# Sheet1_MCU.net
KiCad netlist of a schematic drawn in Altium Designer
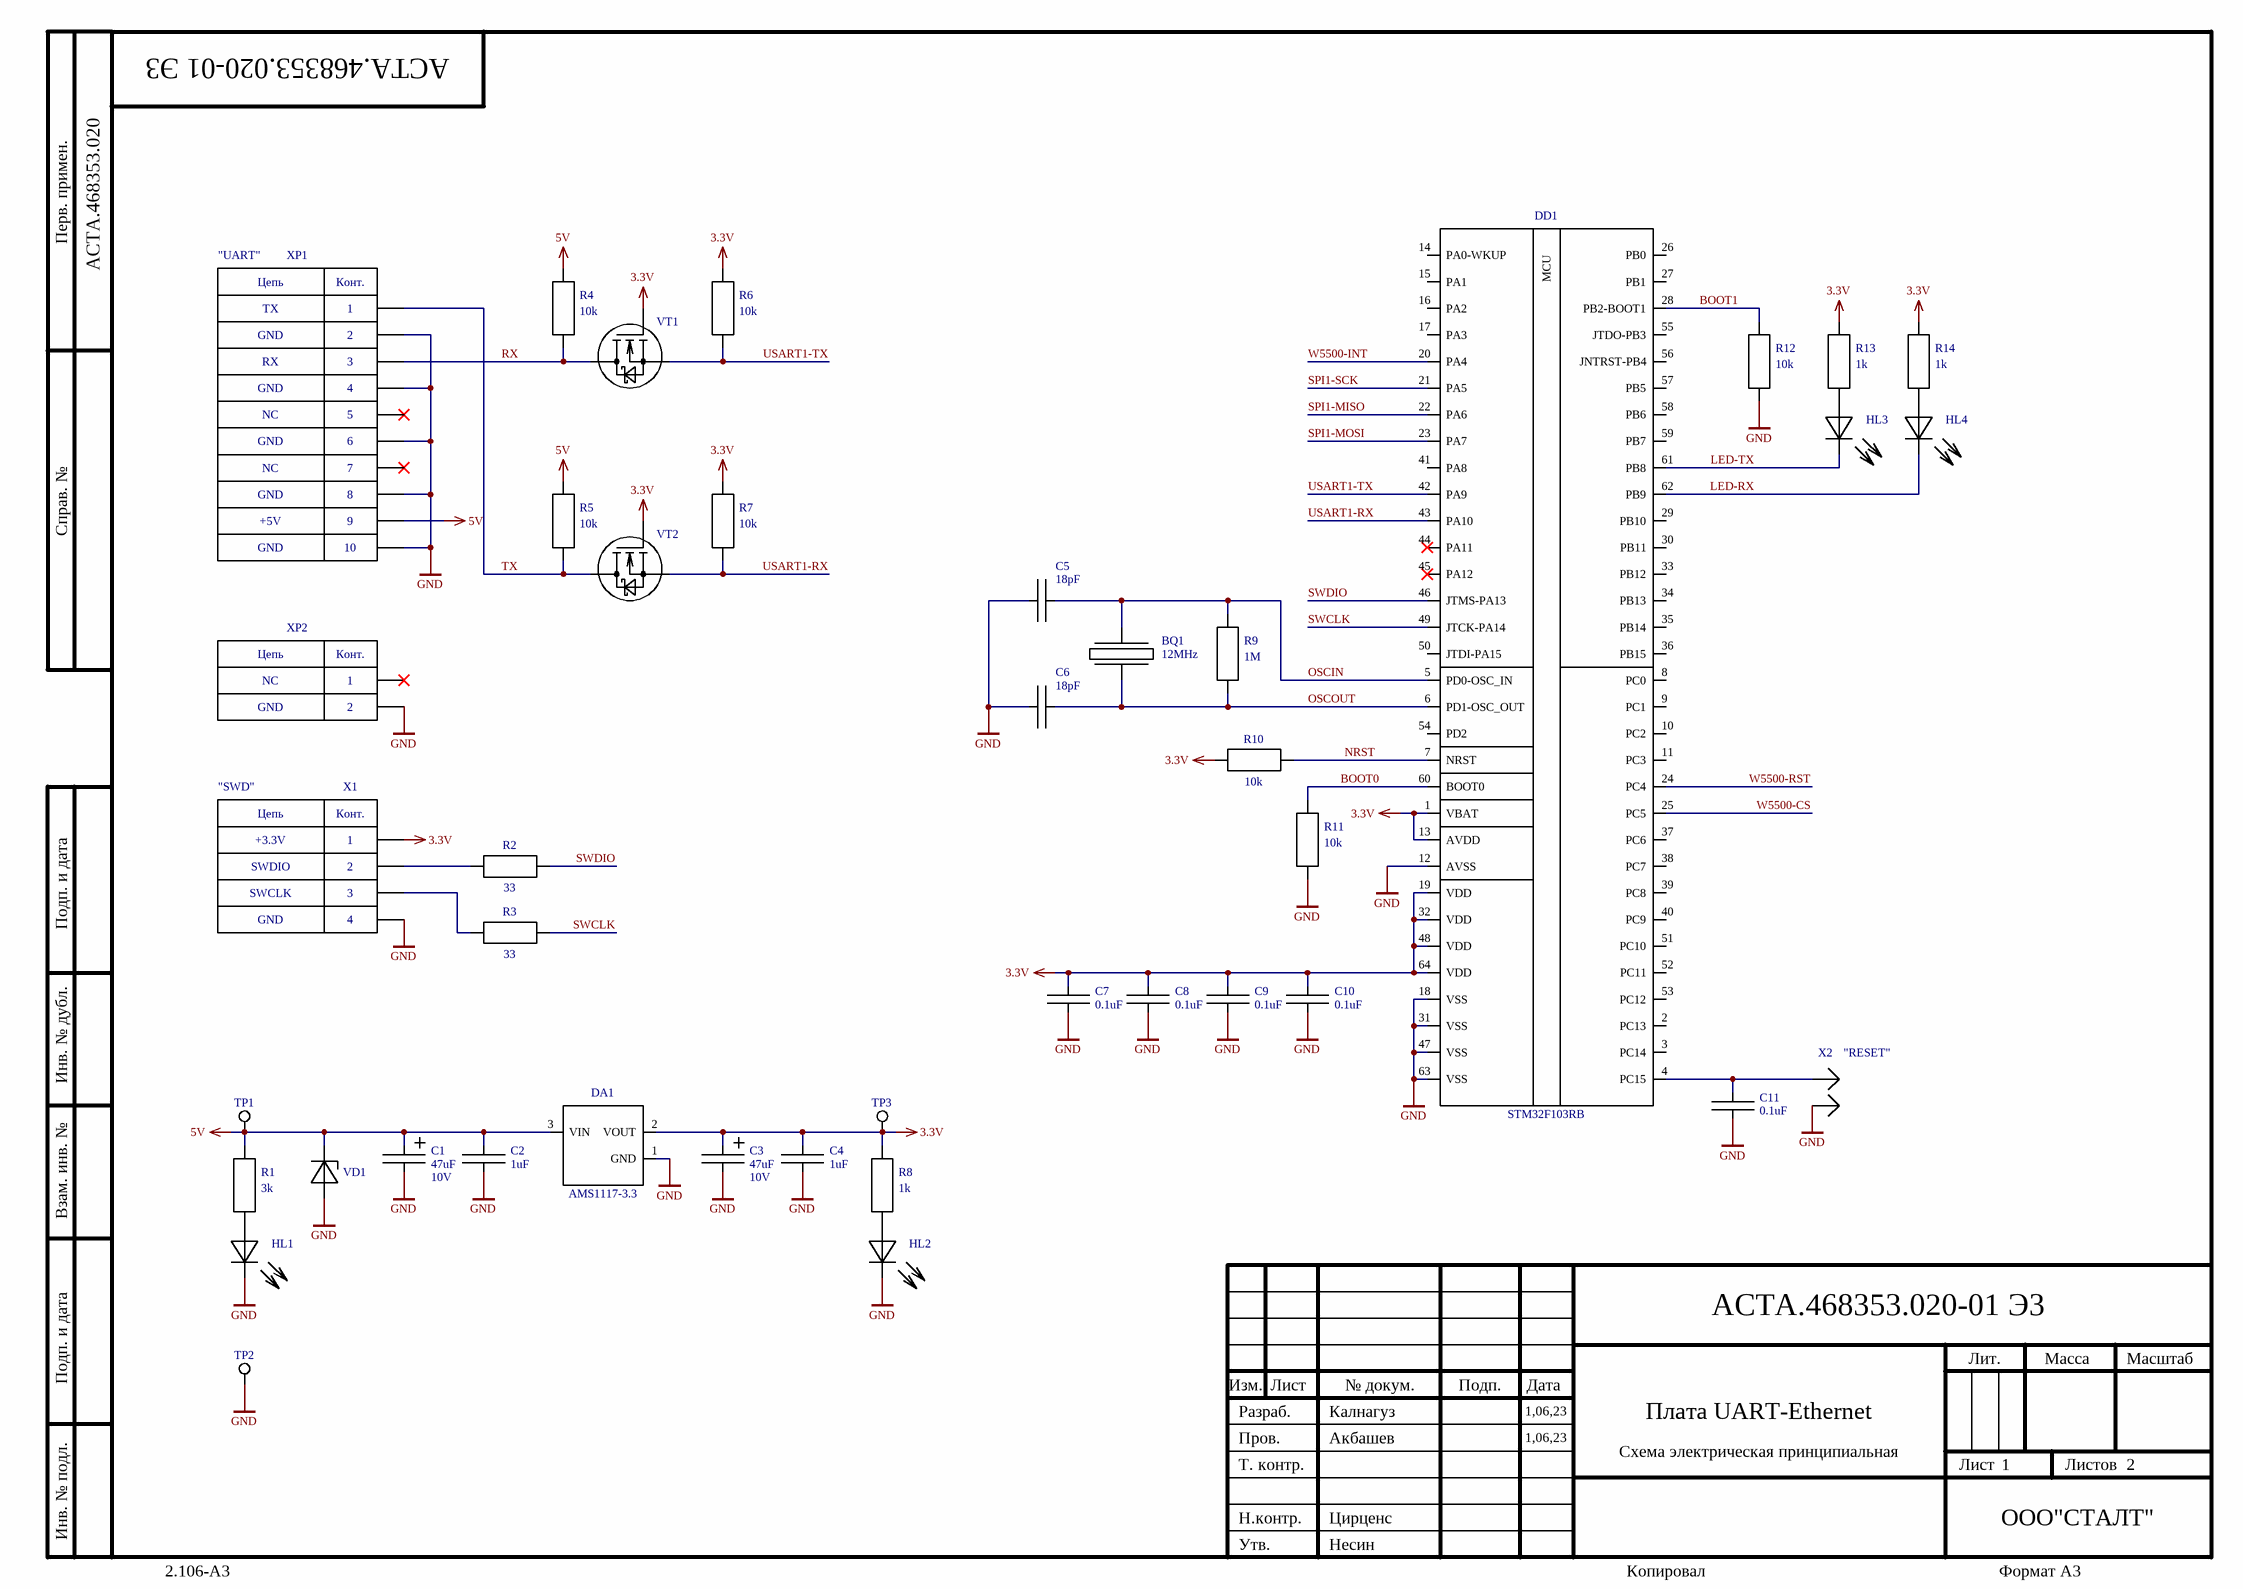
[diagram p0: Sheet1_MCU.SchDoc]

(export (version "E")
  (design (tool "Eeschema 10.0.6"))
  (components
    (comp (ref "BQ1")
      (value "12MHz")
      (footprint "HT-49S")
      (fields (field (name "Comment") "HT-49S_Rated"))
      (libsource (lib "Resonators") (part "HT-49S_Rated"))
    )
    (comp (ref "C1")
      (value "47uF")
      (footprint "CaseB_TantalumCap")
      (fields (field (name "VOLTAGE") "10V") (field (name "Comment") "CaseB_TantalumCap"))
      (libsource (lib "Tantalum_Capacitors") (part "CaseB_TantalumCap"))
    )
    (comp (ref "C2")
      (value "1uF")
      (footprint "CAP0805")
      (fields (field (name "Comment") "CAP0805_Rated"))
      (libsource (lib "Ceramic_Capacitors") (part "CAP0805_Rated"))
    )
    (comp (ref "C3")
      (value "47uF")
      (footprint "CaseB_TantalumCap")
      (fields (field (name "VOLTAGE") "10V") (field (name "Comment") "CaseB_TantalumCap"))
      (libsource (lib "Tantalum_Capacitors") (part "CaseB_TantalumCap"))
    )
    (comp (ref "C4")
      (value "1uF")
      (footprint "CAP0805")
      (fields (field (name "Comment") "CAP0805_Rated"))
      (libsource (lib "Ceramic_Capacitors") (part "CAP0805_Rated"))
    )
    (comp (ref "C5")
      (value "18pF")
      (footprint "CAP0805")
      (fields (field (name "Comment") "CAP0805_Rated"))
      (libsource (lib "Ceramic_Capacitors") (part "CAP0805_Rated"))
    )
    (comp (ref "C6")
      (value "18pF")
      (footprint "CAP0805")
      (fields (field (name "Comment") "CAP0805_Rated"))
      (libsource (lib "Ceramic_Capacitors") (part "CAP0805_Rated"))
    )
    (comp (ref "C7")
      (value "0.1uF")
      (footprint "CAP0805")
      (fields (field (name "Comment") "CAP0805_Rated"))
      (libsource (lib "Ceramic_Capacitors") (part "CAP0805_Rated"))
    )
    (comp (ref "C8")
      (value "0.1uF")
      (footprint "CAP0805")
      (fields (field (name "Comment") "CAP0805_Rated"))
      (libsource (lib "Ceramic_Capacitors") (part "CAP0805_Rated"))
    )
    (comp (ref "C9")
      (value "0.1uF")
      (footprint "CAP0805")
      (fields (field (name "Comment") "CAP0805_Rated"))
      (libsource (lib "Ceramic_Capacitors") (part "CAP0805_Rated"))
    )
    (comp (ref "C10")
      (value "0.1uF")
      (footprint "CAP0805")
      (fields (field (name "Comment") "CAP0805_Rated"))
      (libsource (lib "Ceramic_Capacitors") (part "CAP0805_Rated"))
    )
    (comp (ref "C11")
      (value "0.1uF")
      (footprint "CAP0805")
      (fields (field (name "Comment") "CAP0805_Rated"))
      (libsource (lib "Ceramic_Capacitors") (part "CAP0805_Rated"))
    )
    (comp (ref "DA1")
      (value "AMS1117-3.3")
      (footprint "SOT-223")
      (description "Fixed Voltage 3.3V 1A Low Dropout Voltage Regulator")
      (libsource (lib "Power_Management_ICs") (part "AMS1117-3.3"))
    )
    (comp (ref "DD1")
      (value "STM32F103RB")
      (footprint "LQFP-64")
      (description "ARM Cortex-M3 MCU")
      (libsource (lib "MCU") (part "STM32F103RB"))
    )
    (comp (ref "HL1")
      (value "KPTD-3216MGC")
      (footprint "KPTD-3216 Green")
      (description "3.2x1.6mm SMD LED Mega Green")
      (libsource (lib "LEDs_SMD") (part "KPTD-3216MGC"))
    )
    (comp (ref "HL2")
      (value "KPTD-3216MGC")
      (footprint "KPTD-3216 Green")
      (description "3.2x1.6mm SMD LED Mega Green")
      (libsource (lib "LEDs_SMD") (part "KPTD-3216MGC"))
    )
    (comp (ref "HL3")
      (value "KPTD-3216MGC")
      (footprint "KPTD-3216 Green")
      (description "3.2x1.6mm SMD LED Mega Green")
      (libsource (lib "LEDs_SMD") (part "KPTD-3216MGC"))
    )
    (comp (ref "HL4")
      (value "KPTD-3216SYC")
      (footprint "KPTD-3216 Yellow")
      (description "3.2x1.6mm SMD LED Super Bright Yellow")
      (libsource (lib "LEDs_SMD") (part "KPTD-3216SYC"))
    )
    (comp (ref "R1")
      (value "3k")
      (footprint "RES0805")
      (fields (field (name "TOLERANCE") "5%") (field (name "Comment") "RES0805_Rated"))
      (libsource (lib "Resistors") (part "RES0805_Rated"))
    )
    (comp (ref "R2")
      (value "33")
      (footprint "RES0805")
      (fields (field (name "TOLERANCE") "5%") (field (name "Comment") "RES0805_Rated"))
      (libsource (lib "") (part "RES0805_Rated_1"))
    )
    (comp (ref "R3")
      (value "33")
      (footprint "RES0805")
      (fields (field (name "TOLERANCE") "5%") (field (name "Comment") "RES0805_Rated"))
      (libsource (lib "") (part "RES0805_Rated_1"))
    )
    (comp (ref "R4")
      (value "10k")
      (footprint "RES0805")
      (fields (field (name "TOLERANCE") "5%") (field (name "Comment") "RES0805_Rated"))
      (libsource (lib "Resistors") (part "RES0805_Rated"))
    )
    (comp (ref "R5")
      (value "10k")
      (footprint "RES0805")
      (fields (field (name "TOLERANCE") "5%") (field (name "Comment") "RES0805_Rated"))
      (libsource (lib "Resistors") (part "RES0805_Rated"))
    )
    (comp (ref "R6")
      (value "10k")
      (footprint "RES0805")
      (fields (field (name "TOLERANCE") "5%") (field (name "Comment") "RES0805_Rated"))
      (libsource (lib "Resistors") (part "RES0805_Rated"))
    )
    (comp (ref "R7")
      (value "10k")
      (footprint "RES0805")
      (fields (field (name "TOLERANCE") "5%") (field (name "Comment") "RES0805_Rated"))
      (libsource (lib "Resistors") (part "RES0805_Rated"))
    )
    (comp (ref "R8")
      (value "1k")
      (footprint "RES0805")
      (fields (field (name "TOLERANCE") "5%") (field (name "Comment") "RES0805_Rated"))
      (libsource (lib "Resistors") (part "RES0805_Rated"))
    )
    (comp (ref "R9")
      (value "1M")
      (footprint "RES0805")
      (fields (field (name "TOLERANCE") "5%") (field (name "Comment") "RES0805_Rated"))
      (libsource (lib "Resistors") (part "RES0805_Rated"))
    )
    (comp (ref "R10")
      (value "10k")
      (footprint "RES0805")
      (fields (field (name "TOLERANCE") "5%") (field (name "Comment") "RES0805_Rated"))
      (libsource (lib "") (part "RES0805_Rated_1"))
    )
    (comp (ref "R11")
      (value "10k")
      (footprint "RES0805")
      (fields (field (name "TOLERANCE") "5%") (field (name "Comment") "RES0805_Rated"))
      (libsource (lib "Resistors") (part "RES0805_Rated"))
    )
    (comp (ref "R12")
      (value "10k")
      (footprint "RES0805")
      (fields (field (name "TOLERANCE") "5%") (field (name "Comment") "RES0805_Rated"))
      (libsource (lib "Resistors") (part "RES0805_Rated"))
    )
    (comp (ref "R13")
      (value "1k")
      (footprint "RES0805")
      (fields (field (name "TOLERANCE") "5%") (field (name "Comment") "RES0805_Rated"))
      (libsource (lib "Resistors") (part "RES0805_Rated"))
    )
    (comp (ref "R14")
      (value "1k")
      (footprint "RES0805")
      (fields (field (name "TOLERANCE") "5%") (field (name "Comment") "RES0805_Rated"))
      (libsource (lib "Resistors") (part "RES0805_Rated"))
    )
    (comp (ref "TP1")
      (value "TestPad")
      (footprint "PAD-TH-OCT1x1-0.5")
      (description "TestPoint on PCB")
      (libsource (lib "Connectors") (part "TestPad"))
    )
    (comp (ref "TP2")
      (value "TestPad")
      (footprint "PAD-TH-OCT1x1-0.5")
      (description "TestPoint on PCB")
      (libsource (lib "Connectors") (part "TestPad"))
    )
    (comp (ref "TP3")
      (value "TestPad")
      (footprint "PAD-TH-OCT1x1-0.5")
      (description "TestPoint on PCB")
      (libsource (lib "Connectors") (part "TestPad"))
    )
    (comp (ref "VD1")
      (value "SMAJ5.0A")
      (footprint "SMA (DO-214AC)")
      (description "5Vr 400W 43.5A UniDirectional TVS")
      (libsource (lib "TVS_Diodes") (part "SMAJ5.0A"))
    )
    (comp (ref "VT1")
      (value "BSS138")
      (footprint "SOT-23")
      (description "Small Signal N-Channel MOSFET 50V 220mA")
      (libsource (lib "MOSFETs") (part "BSS138"))
    )
    (comp (ref "VT2")
      (value "BSS138")
      (footprint "SOT-23")
      (description "Small Signal N-Channel MOSFET 50V 220mA")
      (libsource (lib "MOSFETs") (part "BSS138"))
    )
    (comp (ref "X1")
      (value "PBS-4")
      (footprint "PBS-4")
      (description "Female Header Pitch 2.54mm")
      (fields
        (field (name "CIRCUIT4") "GND")
        (field (name "CIRCUIT3") "SWCLK")
        (field (name "CIRCUIT1") "+3.3V")
        (field (name "CIRCUIT2") "SWDIO")
        (field (name "LABEL") "\"SWD\"")
      )
      (libsource (lib "Connectors") (part "PBS-4"))
    )
    (comp (ref "X2")
      (value "PLS-2")
      (footprint "PLS-2")
      (description "Pin Header Pitch 2.54mm")
      (fields (field (name "LABEL") "\"RESET\""))
      (libsource (lib "") (part "PLS-2_1"))
    )
    (comp (ref "XP1")
      (value "PLS-10")
      (footprint "PLS-10")
      (description "Pin Header Pitch 2.54mm")
      (fields
        (field (name "CIRCUIT4") "GND")
        (field (name "CIRCUIT5") "NC")
        (field (name "CIRCUIT6") "GND")
        (field (name "CIRCUIT7") "NC")
        (field (name "CIRCUIT8") "GND")
        (field (name "CIRCUIT9") "+5V")
        (field (name "CIRCUIT10") "GND")
        (field (name "CIRCUIT3") "RX")
        (field (name "CIRCUIT1") "TX")
        (field (name "CIRCUIT2") "GND")
        (field (name "LABEL") "\"UART\"")
      )
      (libsource (lib "Connectors") (part "PLS-10"))
    )
    (comp (ref "XP2")
      (value "PLS-2")
      (footprint "PLS-2")
      (description "Pin Header Pitch 2.54mm")
      (fields (field (name "CIRCUIT1") "NC") (field (name "CIRCUIT2") "GND"))
      (libsource (lib "Connectors") (part "PLS-2"))
    )
  )
  (nets
    (net (code "1") (name "/BOOT0") (class "Default")
      (node (ref "DD1") (pin "60") (pinfunction "BOOT0_60") (pintype "power_in"))
      (node (ref "R11") (pin "2") (pinfunction "2_2") (pintype "passive"))
    )
    (net (code "2") (name "/BOOT1") (class "Default")
      (node (ref "DD1") (pin "28") (pinfunction "PB2-BOOT1_28") (pintype "bidirectional"))
      (node (ref "R12") (pin "2") (pinfunction "2_2") (pintype "passive"))
    )
    (net (code "3") (name "/LED-RX") (class "Default")
      (node (ref "DD1") (pin "62") (pinfunction "PB9_62") (pintype "bidirectional"))
      (node (ref "HL4") (pin "K") (pinfunction "K_K") (pintype "passive"))
    )
    (net (code "4") (name "/LED-TX") (class "Default")
      (node (ref "DD1") (pin "61") (pinfunction "PB8_61") (pintype "bidirectional"))
      (node (ref "HL3") (pin "K") (pinfunction "K_K") (pintype "passive"))
    )
    (net (code "5") (name "/NRST") (class "Default")
      (node (ref "DD1") (pin "7") (pinfunction "NRST_7") (pintype "bidirectional"))
      (node (ref "R10") (pin "2") (pinfunction "2_2") (pintype "passive"))
    )
    (net (code "6") (name "/OSCIN") (class "Default")
      (node (ref "BQ1") (pin "1") (pinfunction "1_1") (pintype "passive"))
      (node (ref "C5") (pin "2") (pinfunction "2_2") (pintype "passive"))
      (node (ref "DD1") (pin "5") (pinfunction "PD0-OSC_IN_5") (pintype "bidirectional"))
      (node (ref "R9") (pin "2") (pinfunction "2_2") (pintype "passive"))
    )
    (net (code "7") (name "/OSCOUT") (class "Default")
      (node (ref "BQ1") (pin "2") (pinfunction "2_2") (pintype "passive"))
      (node (ref "C6") (pin "2") (pinfunction "2_2") (pintype "passive"))
      (node (ref "DD1") (pin "6") (pinfunction "PD1-OSC_OUT_6") (pintype "bidirectional"))
      (node (ref "R9") (pin "1") (pinfunction "1_1") (pintype "passive"))
    )
    (net (code "8") (name "/RX") (class "Default")
      (node (ref "R4") (pin "1") (pinfunction "1_1") (pintype "passive"))
      (node (ref "VT1") (pin "2") (pinfunction "D_2") (pintype "passive"))
      (node (ref "XP1") (pin "3") (pinfunction "3_3") (pintype "passive"))
    )
    (net (code "9") (name "/SPI1-MISO") (class "Default")
      (node (ref "DD1") (pin "22") (pinfunction "PA6_22") (pintype "bidirectional"))
    )
    (net (code "10") (name "/SPI1-MOSI") (class "Default")
      (node (ref "DD1") (pin "23") (pinfunction "PA7_23") (pintype "bidirectional"))
    )
    (net (code "11") (name "/SPI1-SCK") (class "Default")
      (node (ref "DD1") (pin "21") (pinfunction "PA5_21") (pintype "bidirectional"))
    )
    (net (code "12") (name "/SWCLK") (class "Default")
      (node (ref "DD1") (pin "49") (pinfunction "JTCK-PA14_49") (pintype "bidirectional"))
      (node (ref "R3") (pin "2") (pinfunction "2_2") (pintype "passive"))
    )
    (net (code "13") (name "/SWDIO") (class "Default")
      (node (ref "DD1") (pin "46") (pinfunction "JTMS-PA13_46") (pintype "bidirectional"))
      (node (ref "R2") (pin "2") (pinfunction "2_2") (pintype "passive"))
    )
    (net (code "14") (name "/TX") (class "Default")
      (node (ref "R5") (pin "1") (pinfunction "1_1") (pintype "passive"))
      (node (ref "VT2") (pin "2") (pinfunction "D_2") (pintype "passive"))
      (node (ref "XP1") (pin "1") (pinfunction "1_1") (pintype "passive"))
    )
    (net (code "15") (name "/USART1-RX") (class "Default")
      (node (ref "DD1") (pin "43") (pinfunction "PA10_43") (pintype "bidirectional"))
      (node (ref "R7") (pin "1") (pinfunction "1_1") (pintype "passive"))
      (node (ref "VT2") (pin "3") (pinfunction "S_3") (pintype "passive"))
    )
    (net (code "16") (name "/USART1-TX") (class "Default")
      (node (ref "DD1") (pin "42") (pinfunction "PA9_42") (pintype "bidirectional"))
      (node (ref "R6") (pin "1") (pinfunction "1_1") (pintype "passive"))
      (node (ref "VT1") (pin "3") (pinfunction "S_3") (pintype "passive"))
    )
    (net (code "17") (name "/W5500-CS") (class "Default")
      (node (ref "DD1") (pin "25") (pinfunction "PC5_25") (pintype "bidirectional"))
    )
    (net (code "18") (name "/W5500-INT") (class "Default")
      (node (ref "DD1") (pin "20") (pinfunction "PA4_20") (pintype "bidirectional"))
    )
    (net (code "19") (name "/W5500-RST") (class "Default")
      (node (ref "DD1") (pin "24") (pinfunction "PC4_24") (pintype "bidirectional"))
    )
    (net (code "20") (name "3.3V") (class "Default")
      (node (ref "C10") (pin "1") (pinfunction "1_1") (pintype "passive"))
      (node (ref "C3") (pin "1") (pinfunction "+_1") (pintype "passive"))
      (node (ref "C4") (pin "1") (pinfunction "1_1") (pintype "passive"))
      (node (ref "C7") (pin "1") (pinfunction "1_1") (pintype "passive"))
      (node (ref "C8") (pin "1") (pinfunction "1_1") (pintype "passive"))
      (node (ref "C9") (pin "1") (pinfunction "1_1") (pintype "passive"))
      (node (ref "DA1") (pin "2") (pinfunction "VOUT_2") (pintype "power_in"))
      (node (ref "DD1") (pin "1") (pinfunction "VBAT_1") (pintype "power_in"))
      (node (ref "DD1") (pin "13") (pinfunction "AVDD_13") (pintype "power_in"))
      (node (ref "DD1") (pin "19") (pinfunction "VDD_19") (pintype "power_in"))
      (node (ref "DD1") (pin "32") (pinfunction "VDD_32") (pintype "power_in"))
      (node (ref "DD1") (pin "48") (pinfunction "VDD_48") (pintype "power_in"))
      (node (ref "DD1") (pin "64") (pinfunction "VDD_64") (pintype "power_in"))
      (node (ref "R10") (pin "1") (pinfunction "1_1") (pintype "passive"))
      (node (ref "R13") (pin "2") (pinfunction "2_2") (pintype "passive"))
      (node (ref "R14") (pin "2") (pinfunction "2_2") (pintype "passive"))
      (node (ref "R6") (pin "2") (pinfunction "2_2") (pintype "passive"))
      (node (ref "R7") (pin "2") (pinfunction "2_2") (pintype "passive"))
      (node (ref "R8") (pin "2") (pinfunction "2_2") (pintype "passive"))
      (node (ref "TP3") (pin "1") (pinfunction "1_1") (pintype "passive"))
      (node (ref "VT1") (pin "1") (pinfunction "G_1") (pintype "passive"))
      (node (ref "VT2") (pin "1") (pinfunction "G_1") (pintype "passive"))
      (node (ref "X1") (pin "1") (pinfunction "1_1") (pintype "passive"))
    )
    (net (code "21") (name "5V") (class "Default")
      (node (ref "C1") (pin "1") (pinfunction "+_1") (pintype "passive"))
      (node (ref "C2") (pin "1") (pinfunction "1_1") (pintype "passive"))
      (node (ref "DA1") (pin "3") (pinfunction "VIN_3") (pintype "power_in"))
      (node (ref "R1") (pin "2") (pinfunction "2_2") (pintype "passive"))
      (node (ref "R4") (pin "2") (pinfunction "2_2") (pintype "passive"))
      (node (ref "R5") (pin "2") (pinfunction "2_2") (pintype "passive"))
      (node (ref "TP1") (pin "1") (pinfunction "1_1") (pintype "passive"))
      (node (ref "VD1") (pin "K") (pinfunction "K_K") (pintype "passive"))
      (node (ref "XP1") (pin "9") (pinfunction "9_9") (pintype "passive"))
    )
    (net (code "22") (name "GND") (class "Default")
      (node (ref "C1") (pin "2") (pinfunction "-_2") (pintype "passive"))
      (node (ref "C10") (pin "2") (pinfunction "2_2") (pintype "passive"))
      (node (ref "C11") (pin "2") (pinfunction "2_2") (pintype "passive"))
      (node (ref "C2") (pin "2") (pinfunction "2_2") (pintype "passive"))
      (node (ref "C3") (pin "2") (pinfunction "-_2") (pintype "passive"))
      (node (ref "C4") (pin "2") (pinfunction "2_2") (pintype "passive"))
      (node (ref "C5") (pin "1") (pinfunction "1_1") (pintype "passive"))
      (node (ref "C6") (pin "1") (pinfunction "1_1") (pintype "passive"))
      (node (ref "C7") (pin "2") (pinfunction "2_2") (pintype "passive"))
      (node (ref "C8") (pin "2") (pinfunction "2_2") (pintype "passive"))
      (node (ref "C9") (pin "2") (pinfunction "2_2") (pintype "passive"))
      (node (ref "DA1") (pin "1") (pinfunction "GND_1") (pintype "power_in"))
      (node (ref "DD1") (pin "12") (pinfunction "AVSS_12") (pintype "power_in"))
      (node (ref "DD1") (pin "18") (pinfunction "VSS_18") (pintype "power_in"))
      (node (ref "DD1") (pin "31") (pinfunction "VSS_31") (pintype "power_in"))
      (node (ref "DD1") (pin "47") (pinfunction "VSS_47") (pintype "power_in"))
      (node (ref "DD1") (pin "63") (pinfunction "VSS_63") (pintype "power_in"))
      (node (ref "HL1") (pin "K") (pinfunction "K_K") (pintype "passive"))
      (node (ref "HL2") (pin "K") (pinfunction "K_K") (pintype "passive"))
      (node (ref "R11") (pin "1") (pinfunction "1_1") (pintype "passive"))
      (node (ref "R12") (pin "1") (pinfunction "1_1") (pintype "passive"))
      (node (ref "TP2") (pin "1") (pinfunction "1_1") (pintype "passive"))
      (node (ref "VD1") (pin "A") (pinfunction "A_A") (pintype "passive"))
      (node (ref "X1") (pin "4") (pinfunction "4_4") (pintype "passive"))
      (node (ref "X2") (pin "2") (pinfunction "2_2") (pintype "passive"))
      (node (ref "XP1") (pin "10") (pinfunction "10_10") (pintype "passive"))
      (node (ref "XP1") (pin "2") (pinfunction "2_2") (pintype "passive"))
      (node (ref "XP1") (pin "4") (pinfunction "4_4") (pintype "passive"))
      (node (ref "XP1") (pin "6") (pinfunction "6_6") (pintype "passive"))
      (node (ref "XP1") (pin "8") (pinfunction "8_8") (pintype "passive"))
      (node (ref "XP2") (pin "2") (pinfunction "2_2") (pintype "passive"))
    )
    (net (code "23") (name "Net-(DD1-PC15)") (class "Default")
      (node (ref "C11") (pin "1") (pinfunction "1_1") (pintype "passive"))
      (node (ref "DD1") (pin "4") (pinfunction "PC15_4") (pintype "bidirectional"))
      (node (ref "X2") (pin "1") (pinfunction "1_1") (pintype "passive"))
    )
    (net (code "24") (name "Net-(HL1-PadA)") (class "Default")
      (node (ref "HL1") (pin "A") (pinfunction "A_A") (pintype "passive"))
      (node (ref "R1") (pin "1") (pinfunction "1_1") (pintype "passive"))
    )
    (net (code "25") (name "Net-(HL2-PadA)") (class "Default")
      (node (ref "HL2") (pin "A") (pinfunction "A_A") (pintype "passive"))
      (node (ref "R8") (pin "1") (pinfunction "1_1") (pintype "passive"))
    )
    (net (code "26") (name "Net-(HL3-PadA)") (class "Default")
      (node (ref "HL3") (pin "A") (pinfunction "A_A") (pintype "passive"))
      (node (ref "R13") (pin "1") (pinfunction "1_1") (pintype "passive"))
    )
    (net (code "27") (name "Net-(HL4-PadA)") (class "Default")
      (node (ref "HL4") (pin "A") (pinfunction "A_A") (pintype "passive"))
      (node (ref "R14") (pin "1") (pinfunction "1_1") (pintype "passive"))
    )
    (net (code "28") (name "Net-(R2-Pad1)") (class "Default")
      (node (ref "R2") (pin "1") (pinfunction "1_1") (pintype "passive"))
      (node (ref "X1") (pin "2") (pinfunction "2_2") (pintype "passive"))
    )
    (net (code "29") (name "Net-(R3-Pad1)") (class "Default")
      (node (ref "R3") (pin "1") (pinfunction "1_1") (pintype "passive"))
      (node (ref "X1") (pin "3") (pinfunction "3_3") (pintype "passive"))
    )
    (net (code "30") (name "unconnected-(DD1-JNTRST-PB4-Pad56)") (class "Default")
      (node (ref "DD1") (pin "56") (pinfunction "JNTRST-PB4_56") (pintype "bidirectional"))
    )
    (net (code "31") (name "unconnected-(DD1-JTDI-PA15-Pad50)") (class "Default")
      (node (ref "DD1") (pin "50") (pinfunction "JTDI-PA15_50") (pintype "bidirectional"))
    )
    (net (code "32") (name "unconnected-(DD1-JTDO-PB3-Pad55)") (class "Default")
      (node (ref "DD1") (pin "55") (pinfunction "JTDO-PB3_55") (pintype "bidirectional"))
    )
    (net (code "33") (name "unconnected-(DD1-PA0-WKUP-Pad14)") (class "Default")
      (node (ref "DD1") (pin "14") (pinfunction "PA0-WKUP_14") (pintype "bidirectional"))
    )
    (net (code "34") (name "unconnected-(DD1-PA1-Pad15)") (class "Default")
      (node (ref "DD1") (pin "15") (pinfunction "PA1_15") (pintype "bidirectional"))
    )
    (net (code "35") (name "unconnected-(DD1-PA2-Pad16)") (class "Default")
      (node (ref "DD1") (pin "16") (pinfunction "PA2_16") (pintype "bidirectional"))
    )
    (net (code "36") (name "unconnected-(DD1-PA3-Pad17)") (class "Default")
      (node (ref "DD1") (pin "17") (pinfunction "PA3_17") (pintype "bidirectional"))
    )
    (net (code "37") (name "unconnected-(DD1-PA8-Pad41)") (class "Default")
      (node (ref "DD1") (pin "41") (pinfunction "PA8_41") (pintype "bidirectional"))
    )
    (net (code "38") (name "unconnected-(DD1-PA11-Pad44)") (class "Default")
      (node (ref "DD1") (pin "44") (pinfunction "PA11_44") (pintype "bidirectional+no_connect"))
    )
    (net (code "39") (name "unconnected-(DD1-PA12-Pad45)") (class "Default")
      (node (ref "DD1") (pin "45") (pinfunction "PA12_45") (pintype "bidirectional+no_connect"))
    )
    (net (code "40") (name "unconnected-(DD1-PB0-Pad26)") (class "Default")
      (node (ref "DD1") (pin "26") (pinfunction "PB0_26") (pintype "bidirectional"))
    )
    (net (code "41") (name "unconnected-(DD1-PB1-Pad27)") (class "Default")
      (node (ref "DD1") (pin "27") (pinfunction "PB1_27") (pintype "bidirectional"))
    )
    (net (code "42") (name "unconnected-(DD1-PB5-Pad57)") (class "Default")
      (node (ref "DD1") (pin "57") (pinfunction "PB5_57") (pintype "bidirectional"))
    )
    (net (code "43") (name "unconnected-(DD1-PB6-Pad58)") (class "Default")
      (node (ref "DD1") (pin "58") (pinfunction "PB6_58") (pintype "bidirectional"))
    )
    (net (code "44") (name "unconnected-(DD1-PB7-Pad59)") (class "Default")
      (node (ref "DD1") (pin "59") (pinfunction "PB7_59") (pintype "bidirectional"))
    )
    (net (code "45") (name "unconnected-(DD1-PB10-Pad29)") (class "Default")
      (node (ref "DD1") (pin "29") (pinfunction "PB10_29") (pintype "bidirectional"))
    )
    (net (code "46") (name "unconnected-(DD1-PB11-Pad30)") (class "Default")
      (node (ref "DD1") (pin "30") (pinfunction "PB11_30") (pintype "bidirectional"))
    )
    (net (code "47") (name "unconnected-(DD1-PB12-Pad33)") (class "Default")
      (node (ref "DD1") (pin "33") (pinfunction "PB12_33") (pintype "bidirectional"))
    )
    (net (code "48") (name "unconnected-(DD1-PB13-Pad34)") (class "Default")
      (node (ref "DD1") (pin "34") (pinfunction "PB13_34") (pintype "bidirectional"))
    )
    (net (code "49") (name "unconnected-(DD1-PB14-Pad35)") (class "Default")
      (node (ref "DD1") (pin "35") (pinfunction "PB14_35") (pintype "bidirectional"))
    )
    (net (code "50") (name "unconnected-(DD1-PB15-Pad36)") (class "Default")
      (node (ref "DD1") (pin "36") (pinfunction "PB15_36") (pintype "bidirectional"))
    )
    (net (code "51") (name "unconnected-(DD1-PC0-Pad8)") (class "Default")
      (node (ref "DD1") (pin "8") (pinfunction "PC0_8") (pintype "bidirectional"))
    )
    (net (code "52") (name "unconnected-(DD1-PC1-Pad9)") (class "Default")
      (node (ref "DD1") (pin "9") (pinfunction "PC1_9") (pintype "bidirectional"))
    )
    (net (code "53") (name "unconnected-(DD1-PC2-Pad10)") (class "Default")
      (node (ref "DD1") (pin "10") (pinfunction "PC2_10") (pintype "bidirectional"))
    )
    (net (code "54") (name "unconnected-(DD1-PC3-Pad11)") (class "Default")
      (node (ref "DD1") (pin "11") (pinfunction "PC3_11") (pintype "bidirectional"))
    )
    (net (code "55") (name "unconnected-(DD1-PC6-Pad37)") (class "Default")
      (node (ref "DD1") (pin "37") (pinfunction "PC6_37") (pintype "bidirectional"))
    )
    (net (code "56") (name "unconnected-(DD1-PC7-Pad38)") (class "Default")
      (node (ref "DD1") (pin "38") (pinfunction "PC7_38") (pintype "bidirectional"))
    )
    (net (code "57") (name "unconnected-(DD1-PC8-Pad39)") (class "Default")
      (node (ref "DD1") (pin "39") (pinfunction "PC8_39") (pintype "bidirectional"))
    )
    (net (code "58") (name "unconnected-(DD1-PC9-Pad40)") (class "Default")
      (node (ref "DD1") (pin "40") (pinfunction "PC9_40") (pintype "bidirectional"))
    )
    (net (code "59") (name "unconnected-(DD1-PC10-Pad51)") (class "Default")
      (node (ref "DD1") (pin "51") (pinfunction "PC10_51") (pintype "bidirectional"))
    )
    (net (code "60") (name "unconnected-(DD1-PC11-Pad52)") (class "Default")
      (node (ref "DD1") (pin "52") (pinfunction "PC11_52") (pintype "bidirectional"))
    )
    (net (code "61") (name "unconnected-(DD1-PC12-Pad53)") (class "Default")
      (node (ref "DD1") (pin "53") (pinfunction "PC12_53") (pintype "bidirectional"))
    )
    (net (code "62") (name "unconnected-(DD1-PC13-Pad2)") (class "Default")
      (node (ref "DD1") (pin "2") (pinfunction "PC13_2") (pintype "bidirectional"))
    )
    (net (code "63") (name "unconnected-(DD1-PC14-Pad3)") (class "Default")
      (node (ref "DD1") (pin "3") (pinfunction "PC14_3") (pintype "bidirectional"))
    )
    (net (code "64") (name "unconnected-(DD1-PD2-Pad54)") (class "Default")
      (node (ref "DD1") (pin "54") (pinfunction "PD2_54") (pintype "bidirectional"))
    )
    (net (code "65") (name "unconnected-(XP1-Pad5)") (class "Default")
      (node (ref "XP1") (pin "5") (pinfunction "5_5") (pintype "passive+no_connect"))
    )
    (net (code "66") (name "unconnected-(XP1-Pad7)") (class "Default")
      (node (ref "XP1") (pin "7") (pinfunction "7_7") (pintype "passive+no_connect"))
    )
    (net (code "67") (name "unconnected-(XP2-Pad1)") (class "Default")
      (node (ref "XP2") (pin "1") (pinfunction "1_1") (pintype "passive+no_connect"))
    )
  )
)
